# FPGA_Bank_2.net
KiCad netlist of a schematic drawn in Altium Designer
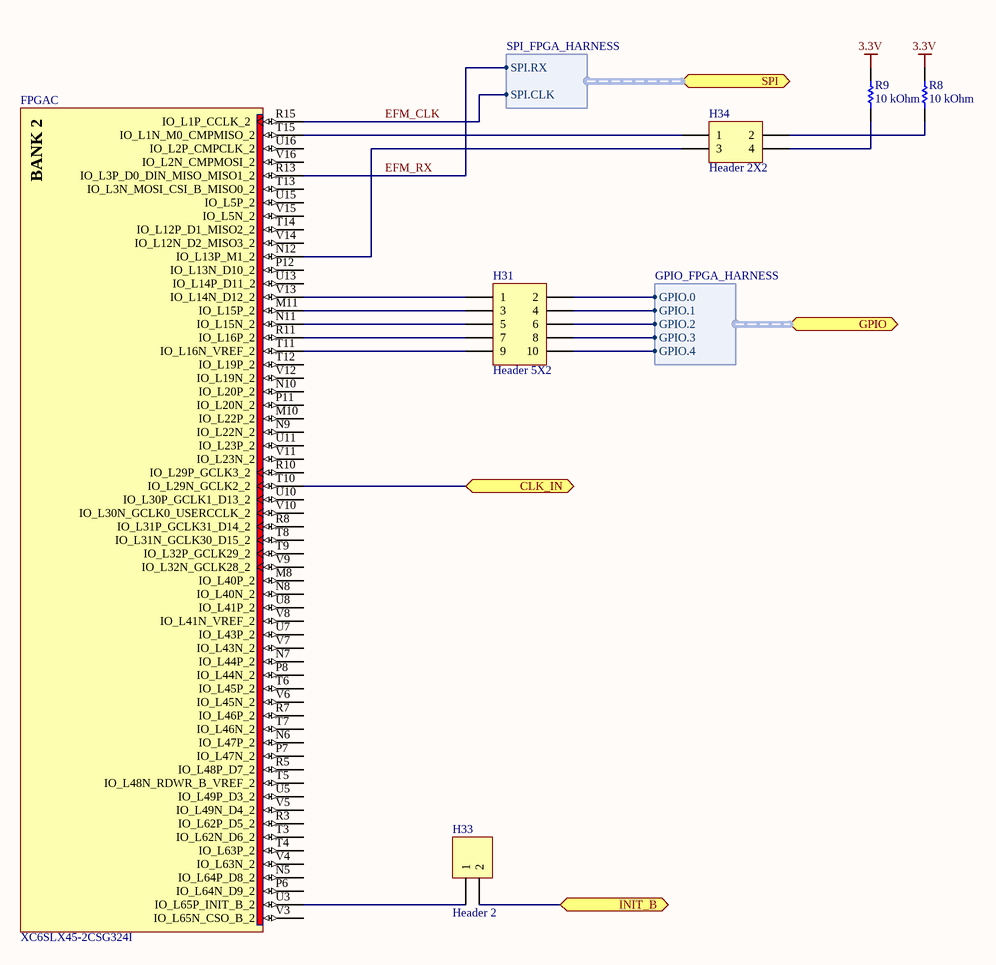
[diagram p0: FPGA Bank 2.SchDoc]

(export (version "E")
  (design (tool "Eeschema 10.0.6"))
  (components
    (comp (ref "FPGA")
      (value "XC6SLX45-2CSG324I")
      (footprint "CSG324")
      (fields (field (name "PUBLISHER") "Altium Limited"))
      (libsource (lib "Xilinx Spartan-6") (part "XC6SLX45-2CSG324I"))
    )
    (comp (ref "H31")
      (value "Header 5X2")
      (footprint "HDR2X5")
      (description "Header, 5-Pin, Dual row")
      (fields (field (name "PUBLISHER") "Altium Limited"))
      (libsource (lib "Miscellaneous Connectors") (part "Header 5X2"))
    )
    (comp (ref "H33")
      (value "Header 2")
      (footprint "HDR1X2")
      (description "Header, 2-Pin")
      (fields (field (name "PUBLISHER") "Altium Limited"))
      (libsource (lib "Miscellaneous Connectors") (part "Header 2"))
    )
    (comp (ref "H34")
      (value "Header 2X2")
      (footprint "HDR2X2")
      (description "Header, 2-Pin, Dual row")
      (fields (field (name "PUBLISHER") "Altium Limited"))
      (libsource (lib "Miscellaneous Connectors") (part "Header 2X2"))
    )
    (comp (ref "R8")
      (value "10 kOhm")
      (footprint "RESC0603(1608)_M")
      (description "1R 0.1W 5% 0603 (1608 Metric)  SMD")
      (fields (field (name "POWER") "0.1 W") (field (name "TOLERANCE") "5 %"))
      (libsource (lib "Altium Content Vault") (part "CMP-1012-00002-1"))
    )
    (comp (ref "R9")
      (value "10 kOhm")
      (footprint "RESC0603(1608)_M")
      (description "1R 0.1W 5% 0603 (1608 Metric)  SMD")
      (fields (field (name "POWER") "0.1 W") (field (name "TOLERANCE") "5 %"))
      (libsource (lib "Altium Content Vault") (part "CMP-1012-00002-1"))
    )
  )
  (nets
    (net (code "3") (name "/CLK_IN") (class "Default")
      (node (ref "FPGA") (pin "T10") (pinfunction "IO_L29N_GCLK2_2_T10") (pintype "bidirectional"))
    )
    (net (code "4") (name "/EFM_CLK") (class "Default")
      (node (ref "FPGA") (pin "R15") (pinfunction "IO_L1P_CCLK_2_R15") (pintype "bidirectional"))
    )
    (net (code "5") (name "/EFM_RX") (class "Default")
      (node (ref "FPGA") (pin "R13") (pinfunction "IO_L3P_D0_DIN_MISO_MISO1_2_R13") (pintype "bidirectional"))
    )
    (net (code "6") (name "/GPIO.0") (class "Default")
      (node (ref "H31") (pin "2") (pinfunction "2_2") (pintype "passive"))
    )
    (net (code "7") (name "/GPIO.1") (class "Default")
      (node (ref "H31") (pin "4") (pinfunction "4_4") (pintype "passive"))
    )
    (net (code "8") (name "/GPIO.2") (class "Default")
      (node (ref "H31") (pin "6") (pinfunction "6_6") (pintype "passive"))
    )
    (net (code "9") (name "/GPIO.3") (class "Default")
      (node (ref "H31") (pin "8") (pinfunction "8_8") (pintype "passive"))
    )
    (net (code "10") (name "/GPIO.4") (class "Default")
      (node (ref "H31") (pin "10") (pinfunction "10_10") (pintype "passive"))
    )
    (net (code "11") (name "/INIT_B") (class "Default")
      (node (ref "H33") (pin "2") (pinfunction "2_2") (pintype "passive"))
    )
    (net (code "14") (name "3.3V") (class "Default")
      (node (ref "R8") (pin "2") (pinfunction "2_2") (pintype "passive"))
      (node (ref "R9") (pin "2") (pinfunction "2_2") (pintype "passive"))
    )
    (net (code "15") (name "Net-(FPGAC-IO_L1N_M0_CMPMISO_2)") (class "Default")
      (node (ref "FPGA") (pin "T15") (pinfunction "IO_L1N_M0_CMPMISO_2_T15") (pintype "bidirectional"))
      (node (ref "H34") (pin "1") (pinfunction "1_1") (pintype "passive"))
    )
    (net (code "16") (name "Net-(FPGAC-IO_L13P_M1_2)") (class "Default")
      (node (ref "FPGA") (pin "N12") (pinfunction "IO_L13P_M1_2_N12") (pintype "bidirectional"))
      (node (ref "H34") (pin "3") (pinfunction "3_3") (pintype "passive"))
    )
    (net (code "17") (name "Net-(FPGAC-IO_L14N_D12_2)") (class "Default")
      (node (ref "FPGA") (pin "V13") (pinfunction "IO_L14N_D12_2_V13") (pintype "bidirectional"))
      (node (ref "H31") (pin "1") (pinfunction "1_1") (pintype "passive"))
    )
    (net (code "18") (name "Net-(FPGAC-IO_L15N_2)") (class "Default")
      (node (ref "FPGA") (pin "N11") (pinfunction "IO_L15N_2_N11") (pintype "bidirectional"))
      (node (ref "H31") (pin "5") (pinfunction "5_5") (pintype "passive"))
    )
    (net (code "19") (name "Net-(FPGAC-IO_L15P_2)") (class "Default")
      (node (ref "FPGA") (pin "M11") (pinfunction "IO_L15P_2_M11") (pintype "bidirectional"))
      (node (ref "H31") (pin "3") (pinfunction "3_3") (pintype "passive"))
    )
    (net (code "20") (name "Net-(FPGAC-IO_L16N_VREF_2)") (class "Default")
      (node (ref "FPGA") (pin "T11") (pinfunction "IO_L16N_VREF_2_T11") (pintype "bidirectional"))
      (node (ref "H31") (pin "9") (pinfunction "9_9") (pintype "passive"))
    )
    (net (code "21") (name "Net-(FPGAC-IO_L16P_2)") (class "Default")
      (node (ref "FPGA") (pin "R11") (pinfunction "IO_L16P_2_R11") (pintype "bidirectional"))
      (node (ref "H31") (pin "7") (pinfunction "7_7") (pintype "passive"))
    )
    (net (code "22") (name "Net-(FPGAC-IO_L65P_INIT_B_2)") (class "Default")
      (node (ref "FPGA") (pin "U3") (pinfunction "IO_L65P_INIT_B_2_U3") (pintype "bidirectional"))
      (node (ref "H33") (pin "1") (pinfunction "1_1") (pintype "passive"))
    )
    (net (code "23") (name "Net-(H34-Pad2)") (class "Default")
      (node (ref "H34") (pin "2") (pinfunction "2_2") (pintype "passive"))
      (node (ref "R8") (pin "1") (pinfunction "1_1") (pintype "passive"))
    )
    (net (code "24") (name "Net-(H34-Pad4)") (class "Default")
      (node (ref "H34") (pin "4") (pinfunction "4_4") (pintype "passive"))
      (node (ref "R9") (pin "1") (pinfunction "1_1") (pintype "passive"))
    )
    (net (code "25") (name "unconnected-(FPGAC-IO_L2N_CMPMOSI_2-PadV16)") (class "Default")
      (node (ref "FPGA") (pin "V16") (pinfunction "IO_L2N_CMPMOSI_2_V16") (pintype "bidirectional"))
    )
    (net (code "26") (name "unconnected-(FPGAC-IO_L2P_CMPCLK_2-PadU16)") (class "Default")
      (node (ref "FPGA") (pin "U16") (pinfunction "IO_L2P_CMPCLK_2_U16") (pintype "bidirectional"))
    )
    (net (code "27") (name "unconnected-(FPGAC-IO_L3N_MOSI_CSI_B_MISO0_2-PadT13)") (class "Default")
      (node (ref "FPGA") (pin "T13") (pinfunction "IO_L3N_MOSI_CSI_B_MISO0_2_T13") (pintype "bidirectional"))
    )
    (net (code "28") (name "unconnected-(FPGAC-IO_L5N_2-PadV15)") (class "Default")
      (node (ref "FPGA") (pin "V15") (pinfunction "IO_L5N_2_V15") (pintype "bidirectional"))
    )
    (net (code "29") (name "unconnected-(FPGAC-IO_L5P_2-PadU15)") (class "Default")
      (node (ref "FPGA") (pin "U15") (pinfunction "IO_L5P_2_U15") (pintype "bidirectional"))
    )
    (net (code "30") (name "unconnected-(FPGAC-IO_L12N_D2_MISO3_2-PadV14)") (class "Default")
      (node (ref "FPGA") (pin "V14") (pinfunction "IO_L12N_D2_MISO3_2_V14") (pintype "bidirectional"))
    )
    (net (code "31") (name "unconnected-(FPGAC-IO_L12P_D1_MISO2_2-PadT14)") (class "Default")
      (node (ref "FPGA") (pin "T14") (pinfunction "IO_L12P_D1_MISO2_2_T14") (pintype "bidirectional"))
    )
    (net (code "32") (name "unconnected-(FPGAC-IO_L13N_D10_2-PadP12)") (class "Default")
      (node (ref "FPGA") (pin "P12") (pinfunction "IO_L13N_D10_2_P12") (pintype "bidirectional"))
    )
    (net (code "33") (name "unconnected-(FPGAC-IO_L14P_D11_2-PadU13)") (class "Default")
      (node (ref "FPGA") (pin "U13") (pinfunction "IO_L14P_D11_2_U13") (pintype "bidirectional"))
    )
    (net (code "34") (name "unconnected-(FPGAC-IO_L19N_2-PadV12)") (class "Default")
      (node (ref "FPGA") (pin "V12") (pinfunction "IO_L19N_2_V12") (pintype "bidirectional"))
    )
    (net (code "35") (name "unconnected-(FPGAC-IO_L19P_2-PadT12)") (class "Default")
      (node (ref "FPGA") (pin "T12") (pinfunction "IO_L19P_2_T12") (pintype "bidirectional"))
    )
    (net (code "36") (name "unconnected-(FPGAC-IO_L20N_2-PadP11)") (class "Default")
      (node (ref "FPGA") (pin "P11") (pinfunction "IO_L20N_2_P11") (pintype "bidirectional"))
    )
    (net (code "37") (name "unconnected-(FPGAC-IO_L20P_2-PadN10)") (class "Default")
      (node (ref "FPGA") (pin "N10") (pinfunction "IO_L20P_2_N10") (pintype "bidirectional"))
    )
    (net (code "38") (name "unconnected-(FPGAC-IO_L22N_2-PadN9)") (class "Default")
      (node (ref "FPGA") (pin "N9") (pinfunction "IO_L22N_2_N9") (pintype "bidirectional"))
    )
    (net (code "39") (name "unconnected-(FPGAC-IO_L22P_2-PadM10)") (class "Default")
      (node (ref "FPGA") (pin "M10") (pinfunction "IO_L22P_2_M10") (pintype "bidirectional"))
    )
    (net (code "40") (name "unconnected-(FPGAC-IO_L23N_2-PadV11)") (class "Default")
      (node (ref "FPGA") (pin "V11") (pinfunction "IO_L23N_2_V11") (pintype "bidirectional"))
    )
    (net (code "41") (name "unconnected-(FPGAC-IO_L23P_2-PadU11)") (class "Default")
      (node (ref "FPGA") (pin "U11") (pinfunction "IO_L23P_2_U11") (pintype "bidirectional"))
    )
    (net (code "42") (name "unconnected-(FPGAC-IO_L29P_GCLK3_2-PadR10)") (class "Default")
      (node (ref "FPGA") (pin "R10") (pinfunction "IO_L29P_GCLK3_2_R10") (pintype "bidirectional"))
    )
    (net (code "43") (name "unconnected-(FPGAC-IO_L30N_GCLK0_USERCCLK_2-PadV10)") (class "Default")
      (node (ref "FPGA") (pin "V10") (pinfunction "IO_L30N_GCLK0_USERCCLK_2_V10") (pintype "bidirectional"))
    )
    (net (code "44") (name "unconnected-(FPGAC-IO_L30P_GCLK1_D13_2-PadU10)") (class "Default")
      (node (ref "FPGA") (pin "U10") (pinfunction "IO_L30P_GCLK1_D13_2_U10") (pintype "bidirectional"))
    )
    (net (code "45") (name "unconnected-(FPGAC-IO_L31N_GCLK30_D15_2-PadT8)") (class "Default")
      (node (ref "FPGA") (pin "T8") (pinfunction "IO_L31N_GCLK30_D15_2_T8") (pintype "bidirectional"))
    )
    (net (code "46") (name "unconnected-(FPGAC-IO_L31P_GCLK31_D14_2-PadR8)") (class "Default")
      (node (ref "FPGA") (pin "R8") (pinfunction "IO_L31P_GCLK31_D14_2_R8") (pintype "bidirectional"))
    )
    (net (code "47") (name "unconnected-(FPGAC-IO_L32N_GCLK28_2-PadV9)") (class "Default")
      (node (ref "FPGA") (pin "V9") (pinfunction "IO_L32N_GCLK28_2_V9") (pintype "bidirectional"))
    )
    (net (code "48") (name "unconnected-(FPGAC-IO_L32P_GCLK29_2-PadT9)") (class "Default")
      (node (ref "FPGA") (pin "T9") (pinfunction "IO_L32P_GCLK29_2_T9") (pintype "bidirectional"))
    )
    (net (code "49") (name "unconnected-(FPGAC-IO_L40N_2-PadN8)") (class "Default")
      (node (ref "FPGA") (pin "N8") (pinfunction "IO_L40N_2_N8") (pintype "bidirectional"))
    )
    (net (code "50") (name "unconnected-(FPGAC-IO_L40P_2-PadM8)") (class "Default")
      (node (ref "FPGA") (pin "M8") (pinfunction "IO_L40P_2_M8") (pintype "bidirectional"))
    )
    (net (code "51") (name "unconnected-(FPGAC-IO_L41N_VREF_2-PadV8)") (class "Default")
      (node (ref "FPGA") (pin "V8") (pinfunction "IO_L41N_VREF_2_V8") (pintype "bidirectional"))
    )
    (net (code "52") (name "unconnected-(FPGAC-IO_L41P_2-PadU8)") (class "Default")
      (node (ref "FPGA") (pin "U8") (pinfunction "IO_L41P_2_U8") (pintype "bidirectional"))
    )
    (net (code "53") (name "unconnected-(FPGAC-IO_L43N_2-PadV7)") (class "Default")
      (node (ref "FPGA") (pin "V7") (pinfunction "IO_L43N_2_V7") (pintype "bidirectional"))
    )
    (net (code "54") (name "unconnected-(FPGAC-IO_L43P_2-PadU7)") (class "Default")
      (node (ref "FPGA") (pin "U7") (pinfunction "IO_L43P_2_U7") (pintype "bidirectional"))
    )
    (net (code "55") (name "unconnected-(FPGAC-IO_L44N_2-PadP8)") (class "Default")
      (node (ref "FPGA") (pin "P8") (pinfunction "IO_L44N_2_P8") (pintype "bidirectional"))
    )
    (net (code "56") (name "unconnected-(FPGAC-IO_L44P_2-PadN7)") (class "Default")
      (node (ref "FPGA") (pin "N7") (pinfunction "IO_L44P_2_N7") (pintype "bidirectional"))
    )
    (net (code "57") (name "unconnected-(FPGAC-IO_L45N_2-PadV6)") (class "Default")
      (node (ref "FPGA") (pin "V6") (pinfunction "IO_L45N_2_V6") (pintype "bidirectional"))
    )
    (net (code "58") (name "unconnected-(FPGAC-IO_L45P_2-PadT6)") (class "Default")
      (node (ref "FPGA") (pin "T6") (pinfunction "IO_L45P_2_T6") (pintype "bidirectional"))
    )
    (net (code "59") (name "unconnected-(FPGAC-IO_L46N_2-PadT7)") (class "Default")
      (node (ref "FPGA") (pin "T7") (pinfunction "IO_L46N_2_T7") (pintype "bidirectional"))
    )
    (net (code "60") (name "unconnected-(FPGAC-IO_L46P_2-PadR7)") (class "Default")
      (node (ref "FPGA") (pin "R7") (pinfunction "IO_L46P_2_R7") (pintype "bidirectional"))
    )
    (net (code "61") (name "unconnected-(FPGAC-IO_L47N_2-PadP7)") (class "Default")
      (node (ref "FPGA") (pin "P7") (pinfunction "IO_L47N_2_P7") (pintype "bidirectional"))
    )
    (net (code "62") (name "unconnected-(FPGAC-IO_L47P_2-PadN6)") (class "Default")
      (node (ref "FPGA") (pin "N6") (pinfunction "IO_L47P_2_N6") (pintype "bidirectional"))
    )
    (net (code "63") (name "unconnected-(FPGAC-IO_L48N_RDWR_B_VREF_2-PadT5)") (class "Default")
      (node (ref "FPGA") (pin "T5") (pinfunction "IO_L48N_RDWR_B_VREF_2_T5") (pintype "bidirectional"))
    )
    (net (code "64") (name "unconnected-(FPGAC-IO_L48P_D7_2-PadR5)") (class "Default")
      (node (ref "FPGA") (pin "R5") (pinfunction "IO_L48P_D7_2_R5") (pintype "bidirectional"))
    )
    (net (code "65") (name "unconnected-(FPGAC-IO_L49N_D4_2-PadV5)") (class "Default")
      (node (ref "FPGA") (pin "V5") (pinfunction "IO_L49N_D4_2_V5") (pintype "bidirectional"))
    )
    (net (code "66") (name "unconnected-(FPGAC-IO_L49P_D3_2-PadU5)") (class "Default")
      (node (ref "FPGA") (pin "U5") (pinfunction "IO_L49P_D3_2_U5") (pintype "bidirectional"))
    )
    (net (code "67") (name "unconnected-(FPGAC-IO_L62N_D6_2-PadT3)") (class "Default")
      (node (ref "FPGA") (pin "T3") (pinfunction "IO_L62N_D6_2_T3") (pintype "bidirectional"))
    )
    (net (code "68") (name "unconnected-(FPGAC-IO_L62P_D5_2-PadR3)") (class "Default")
      (node (ref "FPGA") (pin "R3") (pinfunction "IO_L62P_D5_2_R3") (pintype "bidirectional"))
    )
    (net (code "69") (name "unconnected-(FPGAC-IO_L63N_2-PadV4)") (class "Default")
      (node (ref "FPGA") (pin "V4") (pinfunction "IO_L63N_2_V4") (pintype "bidirectional"))
    )
    (net (code "70") (name "unconnected-(FPGAC-IO_L63P_2-PadT4)") (class "Default")
      (node (ref "FPGA") (pin "T4") (pinfunction "IO_L63P_2_T4") (pintype "bidirectional"))
    )
    (net (code "71") (name "unconnected-(FPGAC-IO_L64N_D9_2-PadP6)") (class "Default")
      (node (ref "FPGA") (pin "P6") (pinfunction "IO_L64N_D9_2_P6") (pintype "bidirectional"))
    )
    (net (code "72") (name "unconnected-(FPGAC-IO_L64P_D8_2-PadN5)") (class "Default")
      (node (ref "FPGA") (pin "N5") (pinfunction "IO_L64P_D8_2_N5") (pintype "bidirectional"))
    )
    (net (code "73") (name "unconnected-(FPGAC-IO_L65N_CSO_B_2-PadV3)") (class "Default")
      (node (ref "FPGA") (pin "V3") (pinfunction "IO_L65N_CSO_B_2_V3") (pintype "bidirectional"))
    )
  )
)
